# D9X_v41.net
KiCad netlist of a schematic drawn in EAGLE
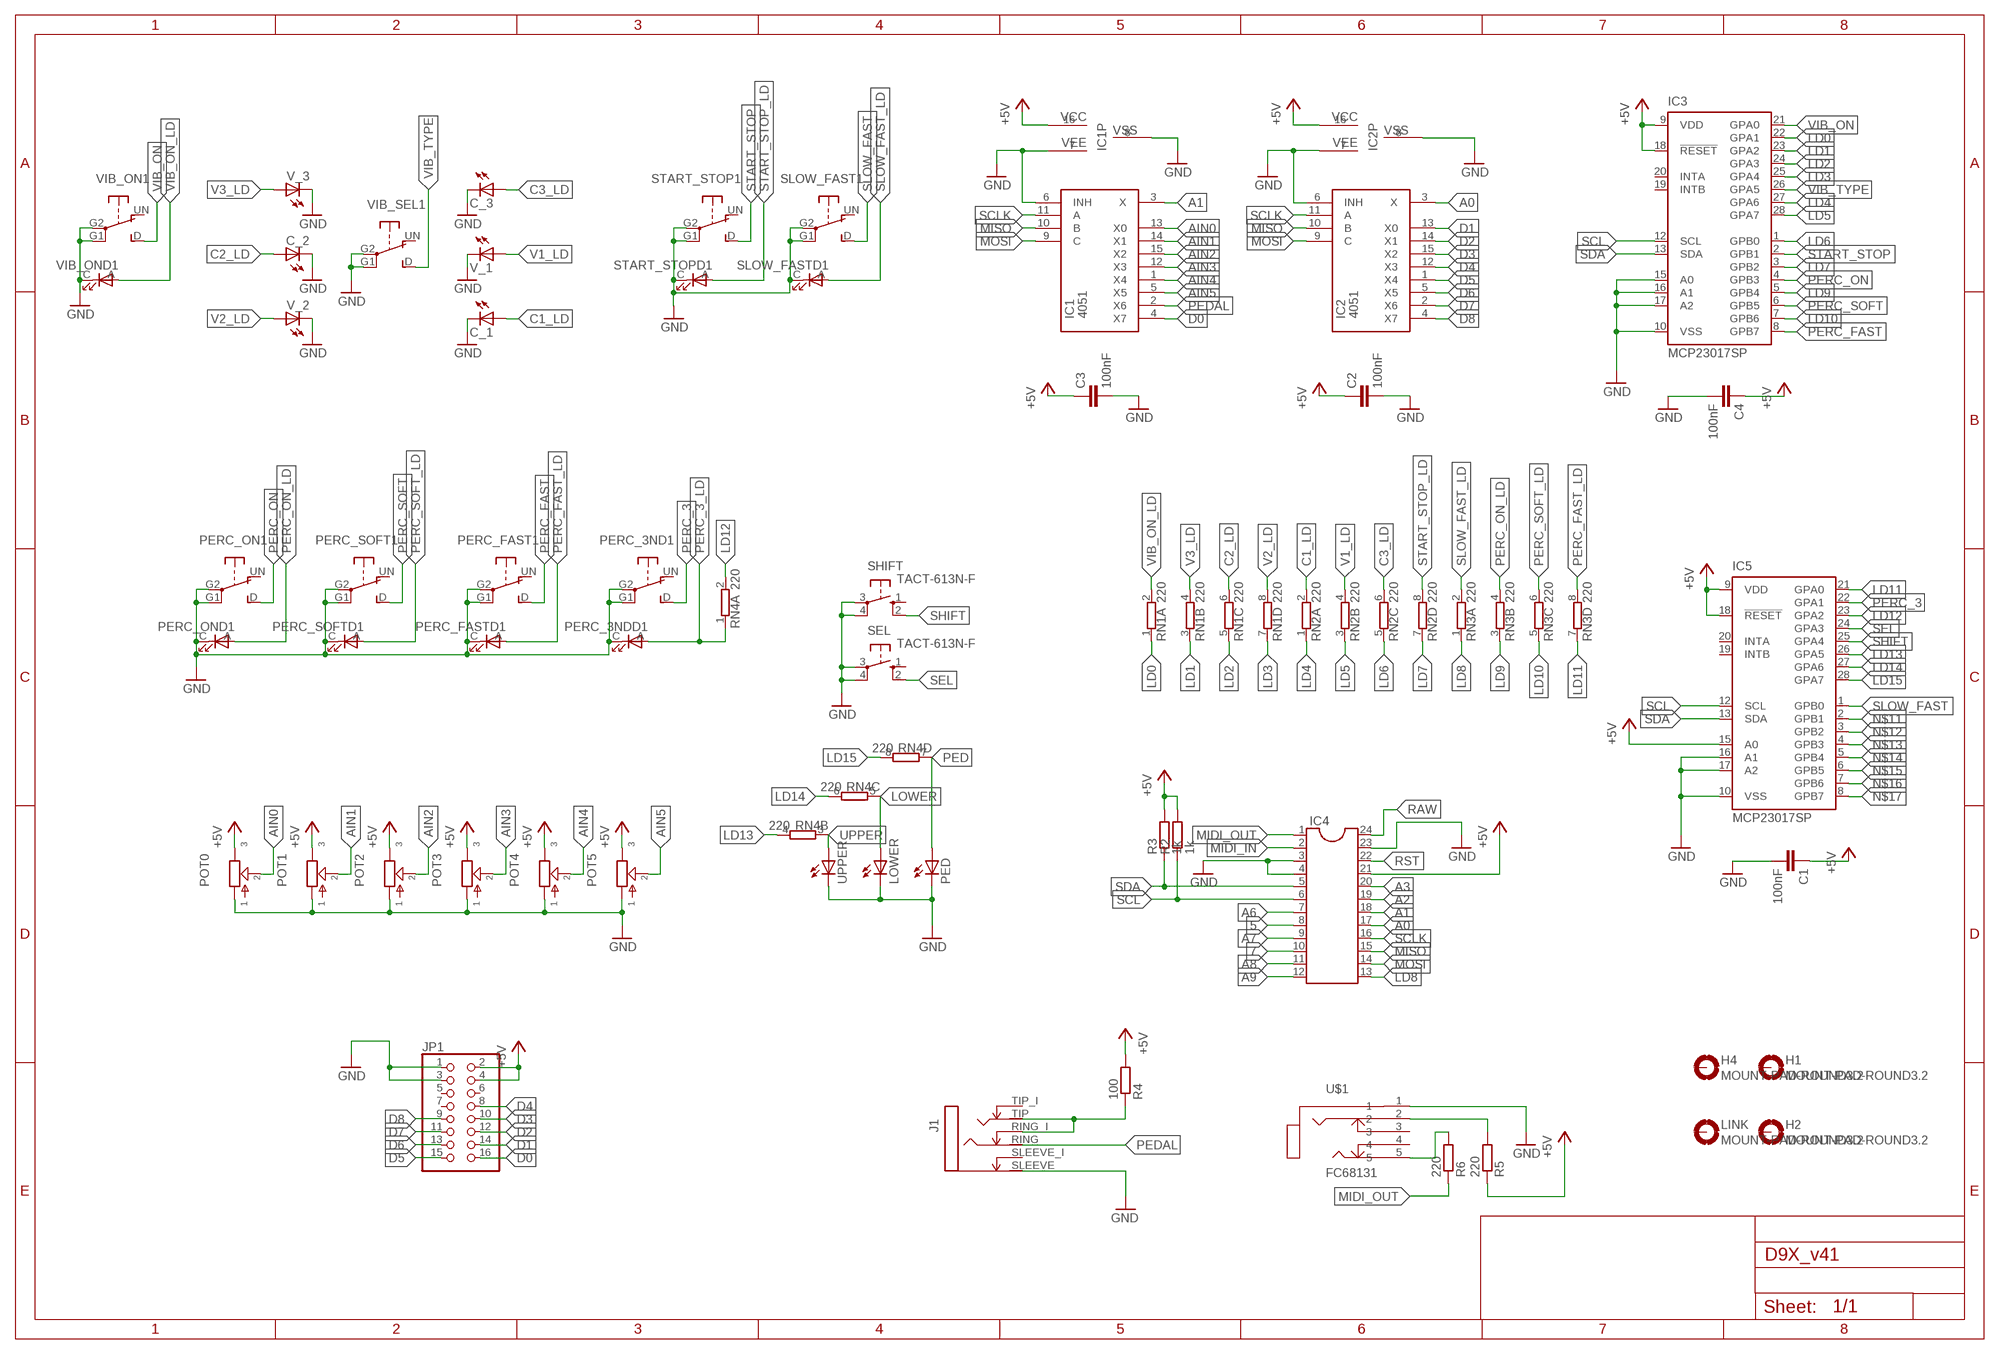
[diagram p0: schematic, sheet 1]

(export (version "E")
  (design (tool "Eeschema 10.0.6"))
  (components
    (comp (ref "C1")
      (value "100nF")
      (footprint "eagle-import:C050-024X044")
      (libsource (lib "eagle-import") (part "C-EU050-024X044"))
    )
    (comp (ref "C2")
      (value "100nF")
      (footprint "eagle-import:C050-024X044")
      (libsource (lib "eagle-import") (part "C-EU050-024X044"))
    )
    (comp (ref "C3")
      (value "100nF")
      (footprint "eagle-import:C050-024X044")
      (libsource (lib "eagle-import") (part "C-EU050-024X044"))
    )
    (comp (ref "C4")
      (value "100nF")
      (footprint "eagle-import:C050-024X044")
      (libsource (lib "eagle-import") (part "C-EU050-024X044"))
    )
    (comp (ref "C_1")
      (value "LED3MM")
      (footprint "eagle-import:LED3MM")
      (libsource (lib "eagle-import") (part "LED3MM"))
    )
    (comp (ref "C_2")
      (value "LED3MM")
      (footprint "eagle-import:LED3MM")
      (libsource (lib "eagle-import") (part "LED3MM"))
    )
    (comp (ref "C_3")
      (value "LED3MM")
      (footprint "eagle-import:LED3MM")
      (libsource (lib "eagle-import") (part "LED3MM"))
    )
    (comp (ref "H1")
      (value "MOUNT-PAD-ROUND3.2")
      (footprint "eagle-import:3,2-PAD")
      (libsource (lib "eagle-import") (part "MOUNT-PAD-ROUND3.2"))
    )
    (comp (ref "H2")
      (value "MOUNT-PAD-ROUND3.2")
      (footprint "eagle-import:3,2-PAD")
      (libsource (lib "eagle-import") (part "MOUNT-PAD-ROUND3.2"))
    )
    (comp (ref "H4")
      (value "MOUNT-PAD-ROUND3.2")
      (footprint "eagle-import:3,2-PAD")
      (libsource (lib "eagle-import") (part "MOUNT-PAD-ROUND3.2"))
    )
    (comp (ref "IC1")
      (value "4051")
      (footprint "eagle-import:DIL16")
      (libsource (lib "eagle-import") (part "4051"))
    )
    (comp (ref "IC2")
      (value "4051")
      (footprint "eagle-import:DIL16")
      (libsource (lib "eagle-import") (part "4051"))
    )
    (comp (ref "IC3")
      (value "MCP23017SP")
      (footprint "eagle-import:DIL28-3")
      (fields (field (name "MF") "MICROCHIP") (field (name "MPN") "MCP23017-E/SP"))
      (libsource (lib "eagle-import") (part "MCP23017SP"))
    )
    (comp (ref "IC4")
      (value "DIL24-6")
      (footprint "eagle-import:DIL24-6")
      (libsource (lib "eagle-import") (part "DIL24-6"))
    )
    (comp (ref "IC5")
      (value "MCP23017SP")
      (footprint "eagle-import:DIL28-3")
      (fields (field (name "MF") "MICROCHIP") (field (name "MPN") "MCP23017-E/SP"))
      (libsource (lib "eagle-import") (part "MCP23017SP"))
    )
    (comp (ref "J1")
      (value "STEREOSWJACK_ST_TRS_INT")
      (footprint "eagle-import:ST_JACK_TRS_INT")
      (libsource (lib "eagle-import") (part "STEREOSWJACK_ST_TRS_INT"))
    )
    (comp (ref "JP1")
      (value "PINHD-2X8")
      (footprint "eagle-import:2X08")
      (libsource (lib "eagle-import") (part "PINHD-2X8"))
    )
    (comp (ref "LINK")
      (value "MOUNT-PAD-ROUND3.2")
      (footprint "eagle-import:3,2-PAD")
      (libsource (lib "eagle-import") (part "MOUNT-PAD-ROUND3.2"))
    )
    (comp (ref "LOWER")
      (value "LED3MM")
      (footprint "eagle-import:LED3MM")
      (libsource (lib "eagle-import") (part "LED3MM"))
    )
    (comp (ref "PED")
      (value "LED3MM")
      (footprint "eagle-import:LED3MM")
      (libsource (lib "eagle-import") (part "LED3MM"))
    )
    (comp (ref "PERC_3ND")
      (value "SRKLSHANPU")
      (footprint "eagle-import:SP86N-A1-5-01")
      (libsource (lib "eagle-import") (part "SRKLSHANPU"))
    )
    (comp (ref "PERC_FAST")
      (value "SRKLSHANPU")
      (footprint "eagle-import:SP86N-A1-5-01")
      (libsource (lib "eagle-import") (part "SRKLSHANPU"))
    )
    (comp (ref "PERC_ON")
      (value "SRKLSHANPU")
      (footprint "eagle-import:SP86N-A1-5-01")
      (libsource (lib "eagle-import") (part "SRKLSHANPU"))
    )
    (comp (ref "PERC_SOFT")
      (value "SRKLSHANPU")
      (footprint "eagle-import:SP86N-A1-5-01")
      (libsource (lib "eagle-import") (part "SRKLSHANPU"))
    )
    (comp (ref "POT0")
      (value "POT-EU12MM")
      (footprint "eagle-import:RV120DF-40B1-(L)K")
      (libsource (lib "eagle-import") (part "POT-EU12MM"))
    )
    (comp (ref "POT1")
      (value "POT-EU12MM")
      (footprint "eagle-import:RV120DF-40B1-(L)K")
      (libsource (lib "eagle-import") (part "POT-EU12MM"))
    )
    (comp (ref "POT2")
      (value "POT-EU12MM")
      (footprint "eagle-import:RV120DF-40B1-(L)K")
      (libsource (lib "eagle-import") (part "POT-EU12MM"))
    )
    (comp (ref "POT3")
      (value "POT-EU12MM")
      (footprint "eagle-import:RV120DF-40B1-(L)K")
      (libsource (lib "eagle-import") (part "POT-EU12MM"))
    )
    (comp (ref "POT4")
      (value "POT-EU12MM")
      (footprint "eagle-import:RV120DF-40B1-(L)K")
      (libsource (lib "eagle-import") (part "POT-EU12MM"))
    )
    (comp (ref "POT5")
      (value "POT-EU12MM")
      (footprint "eagle-import:RV120DF-40B1-(L)K")
      (libsource (lib "eagle-import") (part "POT-EU12MM"))
    )
    (comp (ref "R2")
      (value "1k")
      (footprint "eagle-import:0204_7")
      (libsource (lib "eagle-import") (part "R-EU_0204/7"))
    )
    (comp (ref "R3")
      (value "1k")
      (footprint "eagle-import:0204_7")
      (libsource (lib "eagle-import") (part "R-EU_0204/7"))
    )
    (comp (ref "R4")
      (value "100")
      (footprint "eagle-import:0204_7")
      (libsource (lib "eagle-import") (part "R-EU_0204/7"))
    )
    (comp (ref "R5")
      (value "220")
      (footprint "eagle-import:0204_7")
      (libsource (lib "eagle-import") (part "R-EU_0204/7"))
    )
    (comp (ref "R6")
      (value "220")
      (footprint "eagle-import:0204_7")
      (libsource (lib "eagle-import") (part "R-EU_0204/7"))
    )
    (comp (ref "RN1")
      (value "220")
      (footprint "eagle-import:SIL8")
      (libsource (lib "eagle-import") (part "E4R"))
    )
    (comp (ref "RN2")
      (value "220")
      (footprint "eagle-import:SIL8")
      (libsource (lib "eagle-import") (part "E4R"))
    )
    (comp (ref "RN3")
      (value "220")
      (footprint "eagle-import:SIL8")
      (libsource (lib "eagle-import") (part "E4R"))
    )
    (comp (ref "RN4")
      (value "220")
      (footprint "eagle-import:SIL8")
      (libsource (lib "eagle-import") (part "E4R"))
    )
    (comp (ref "SEL")
      (value "TACT-613N-F")
      (footprint "eagle-import:B3F-10XX")
      (fields (field (name "MPN") "B3F-1000"))
      (libsource (lib "eagle-import") (part "10-XX"))
    )
    (comp (ref "SHIFT")
      (value "TACT-613N-F")
      (footprint "eagle-import:B3F-10XX")
      (fields (field (name "MPN") "B3F-1000"))
      (libsource (lib "eagle-import") (part "10-XX"))
    )
    (comp (ref "SLOW_FAST")
      (value "SRKLSHANPU")
      (footprint "eagle-import:SP86N-A1-5-01")
      (libsource (lib "eagle-import") (part "SRKLSHANPU"))
    )
    (comp (ref "START_STOP")
      (value "SRKLSHANPU")
      (footprint "eagle-import:SP86N-A1-5-01")
      (libsource (lib "eagle-import") (part "SRKLSHANPU"))
    )
    (comp (ref "U$1")
      (value "FC68131")
      (footprint "eagle-import:FC68131-5P")
      (libsource (lib "eagle-import") (part "FC68131"))
    )
    (comp (ref "UPPER")
      (value "LED3MM")
      (footprint "eagle-import:LED3MM")
      (libsource (lib "eagle-import") (part "LED3MM"))
    )
    (comp (ref "VIB_ON")
      (value "SRKLSHANPU")
      (footprint "eagle-import:SP86N-A1-5-01")
      (libsource (lib "eagle-import") (part "SRKLSHANPU"))
    )
    (comp (ref "VIB_SEL")
      (value "SRKLSHANPU")
      (footprint "eagle-import:SP86N-A1-5-01")
      (libsource (lib "eagle-import") (part "SRKLSHANPU"))
    )
    (comp (ref "V_1")
      (value "LED3MM")
      (footprint "eagle-import:LED3MM")
      (libsource (lib "eagle-import") (part "LED3MM"))
    )
    (comp (ref "V_2")
      (value "LED3MM")
      (footprint "eagle-import:LED3MM")
      (libsource (lib "eagle-import") (part "LED3MM"))
    )
    (comp (ref "V_3")
      (value "LED3MM")
      (footprint "eagle-import:LED3MM")
      (libsource (lib "eagle-import") (part "LED3MM"))
    )
  )
  (nets
    (net (code "1") (name "+5V") (class "Default")
      (node (ref "C1") (pin "1") (pinfunction "1_1") (pintype "passive"))
      (node (ref "C2") (pin "1") (pinfunction "1_1") (pintype "passive"))
      (node (ref "C3") (pin "1") (pinfunction "1_1") (pintype "passive"))
      (node (ref "C4") (pin "1") (pinfunction "1_1") (pintype "passive"))
      (node (ref "IC1") (pin "16") (pinfunction "VCC_16") (pintype "power_in"))
      (node (ref "IC2") (pin "16") (pinfunction "VCC_16") (pintype "power_in"))
      (node (ref "IC3") (pin "18") (pinfunction "~{RESET}_18") (pintype "input"))
      (node (ref "IC3") (pin "9") (pinfunction "VDD_9") (pintype "power_in"))
      (node (ref "IC4") (pin "21") (pinfunction "21_21") (pintype "passive"))
      (node (ref "IC5") (pin "15") (pinfunction "A0_15") (pintype "input"))
      (node (ref "IC5") (pin "18") (pinfunction "~{RESET}_18") (pintype "input"))
      (node (ref "IC5") (pin "9") (pinfunction "VDD_9") (pintype "power_in"))
      (node (ref "JP1") (pin "2") (pinfunction "2_2") (pintype "passive"))
      (node (ref "JP1") (pin "4") (pinfunction "4_4") (pintype "passive"))
      (node (ref "POT0") (pin "3") (pinfunction "3_3") (pintype "passive"))
      (node (ref "POT1") (pin "3") (pinfunction "3_3") (pintype "passive"))
      (node (ref "POT2") (pin "3") (pinfunction "3_3") (pintype "passive"))
      (node (ref "POT3") (pin "3") (pinfunction "3_3") (pintype "passive"))
      (node (ref "POT4") (pin "3") (pinfunction "3_3") (pintype "passive"))
      (node (ref "POT5") (pin "3") (pinfunction "3_3") (pintype "passive"))
      (node (ref "R2") (pin "2") (pinfunction "2_2") (pintype "passive"))
      (node (ref "R3") (pin "2") (pinfunction "2_2") (pintype "passive"))
      (node (ref "R4") (pin "2") (pinfunction "2_2") (pintype "passive"))
      (node (ref "R5") (pin "1") (pinfunction "1_1") (pintype "passive"))
    )
    (net (code "2") (name "5") (class "Default")
      (node (ref "IC4") (pin "8") (pinfunction "8_8") (pintype "passive"))
    )
    (net (code "3") (name "7") (class "Default")
      (node (ref "IC4") (pin "10") (pinfunction "10_10") (pintype "passive"))
    )
    (net (code "4") (name "A0") (class "Default")
      (node (ref "IC2") (pin "3") (pinfunction "X_3") (pintype "bidirectional"))
      (node (ref "IC4") (pin "17") (pinfunction "17_17") (pintype "passive"))
    )
    (net (code "5") (name "A1") (class "Default")
      (node (ref "IC1") (pin "3") (pinfunction "X_3") (pintype "bidirectional"))
      (node (ref "IC4") (pin "18") (pinfunction "18_18") (pintype "passive"))
    )
    (net (code "6") (name "A2") (class "Default")
      (node (ref "IC4") (pin "19") (pinfunction "19_19") (pintype "passive"))
    )
    (net (code "7") (name "A3") (class "Default")
      (node (ref "IC4") (pin "20") (pinfunction "20_20") (pintype "passive"))
    )
    (net (code "8") (name "A6") (class "Default")
      (node (ref "IC4") (pin "7") (pinfunction "7_7") (pintype "passive"))
    )
    (net (code "9") (name "A7") (class "Default")
      (node (ref "IC4") (pin "9") (pinfunction "9_9") (pintype "passive"))
    )
    (net (code "10") (name "A8") (class "Default")
      (node (ref "IC4") (pin "11") (pinfunction "11_11") (pintype "passive"))
    )
    (net (code "11") (name "A9") (class "Default")
      (node (ref "IC4") (pin "12") (pinfunction "12_12") (pintype "passive"))
    )
    (net (code "12") (name "AIN0") (class "Default")
      (node (ref "IC1") (pin "13") (pinfunction "X0_13") (pintype "bidirectional"))
      (node (ref "POT0") (pin "2") (pinfunction "2_2") (pintype "passive"))
    )
    (net (code "13") (name "AIN1") (class "Default")
      (node (ref "IC1") (pin "14") (pinfunction "X1_14") (pintype "bidirectional"))
      (node (ref "POT1") (pin "2") (pinfunction "2_2") (pintype "passive"))
    )
    (net (code "14") (name "AIN2") (class "Default")
      (node (ref "IC1") (pin "15") (pinfunction "X2_15") (pintype "bidirectional"))
      (node (ref "POT2") (pin "2") (pinfunction "2_2") (pintype "passive"))
    )
    (net (code "15") (name "AIN3") (class "Default")
      (node (ref "IC1") (pin "12") (pinfunction "X3_12") (pintype "bidirectional"))
      (node (ref "POT3") (pin "2") (pinfunction "2_2") (pintype "passive"))
    )
    (net (code "16") (name "AIN4") (class "Default")
      (node (ref "IC1") (pin "1") (pinfunction "X4_1") (pintype "bidirectional"))
      (node (ref "POT4") (pin "2") (pinfunction "2_2") (pintype "passive"))
    )
    (net (code "17") (name "AIN5") (class "Default")
      (node (ref "IC1") (pin "5") (pinfunction "X5_5") (pintype "bidirectional"))
      (node (ref "POT5") (pin "2") (pinfunction "2_2") (pintype "passive"))
    )
    (net (code "18") (name "C1_LD") (class "Default")
      (node (ref "C_1") (pin "A") (pinfunction "A_A") (pintype "passive"))
      (node (ref "RN2") (pin "2") (pinfunction "2_2") (pintype "passive"))
    )
    (net (code "19") (name "C2_LD") (class "Default")
      (node (ref "C_2") (pin "A") (pinfunction "A_A") (pintype "passive"))
      (node (ref "RN1") (pin "6") (pinfunction "2_6") (pintype "passive"))
    )
    (net (code "20") (name "C3_LD") (class "Default")
      (node (ref "C_3") (pin "A") (pinfunction "A_A") (pintype "passive"))
      (node (ref "RN2") (pin "6") (pinfunction "2_6") (pintype "passive"))
    )
    (net (code "21") (name "D0") (class "Default")
      (node (ref "IC1") (pin "4") (pinfunction "X7_4") (pintype "bidirectional"))
      (node (ref "JP1") (pin "16") (pinfunction "16_16") (pintype "passive"))
    )
    (net (code "22") (name "D1") (class "Default")
      (node (ref "IC2") (pin "13") (pinfunction "X0_13") (pintype "bidirectional"))
      (node (ref "JP1") (pin "14") (pinfunction "14_14") (pintype "passive"))
    )
    (net (code "23") (name "D2") (class "Default")
      (node (ref "IC2") (pin "14") (pinfunction "X1_14") (pintype "bidirectional"))
      (node (ref "JP1") (pin "12") (pinfunction "12_12") (pintype "passive"))
    )
    (net (code "24") (name "D3") (class "Default")
      (node (ref "IC2") (pin "15") (pinfunction "X2_15") (pintype "bidirectional"))
      (node (ref "JP1") (pin "10") (pinfunction "10_10") (pintype "passive"))
    )
    (net (code "25") (name "D4") (class "Default")
      (node (ref "IC2") (pin "12") (pinfunction "X3_12") (pintype "bidirectional"))
      (node (ref "JP1") (pin "8") (pinfunction "8_8") (pintype "passive"))
    )
    (net (code "26") (name "D5") (class "Default")
      (node (ref "IC2") (pin "1") (pinfunction "X4_1") (pintype "bidirectional"))
      (node (ref "JP1") (pin "15") (pinfunction "15_15") (pintype "passive"))
    )
    (net (code "27") (name "D6") (class "Default")
      (node (ref "IC2") (pin "5") (pinfunction "X5_5") (pintype "bidirectional"))
      (node (ref "JP1") (pin "13") (pinfunction "13_13") (pintype "passive"))
    )
    (net (code "28") (name "D7") (class "Default")
      (node (ref "IC2") (pin "2") (pinfunction "X6_2") (pintype "bidirectional"))
      (node (ref "JP1") (pin "11") (pinfunction "11_11") (pintype "passive"))
    )
    (net (code "29") (name "D8") (class "Default")
      (node (ref "IC2") (pin "4") (pinfunction "X7_4") (pintype "bidirectional"))
      (node (ref "JP1") (pin "9") (pinfunction "9_9") (pintype "passive"))
    )
    (net (code "30") (name "GND") (class "Default")
      (node (ref "C1") (pin "2") (pinfunction "2_2") (pintype "passive"))
      (node (ref "C2") (pin "2") (pinfunction "2_2") (pintype "passive"))
      (node (ref "C3") (pin "2") (pinfunction "2_2") (pintype "passive"))
      (node (ref "C4") (pin "2") (pinfunction "2_2") (pintype "passive"))
      (node (ref "C_1") (pin "K") (pinfunction "C_K") (pintype "passive"))
      (node (ref "C_2") (pin "K") (pinfunction "C_K") (pintype "passive"))
      (node (ref "C_3") (pin "K") (pinfunction "C_K") (pintype "passive"))
      (node (ref "IC1") (pin "6") (pinfunction "INH_6") (pintype "input"))
      (node (ref "IC1") (pin "7") (pinfunction "VEE_7") (pintype "power_in"))
      (node (ref "IC1") (pin "8") (pinfunction "VSS_8") (pintype "power_in"))
      (node (ref "IC2") (pin "6") (pinfunction "INH_6") (pintype "input"))
      (node (ref "IC2") (pin "7") (pinfunction "VEE_7") (pintype "power_in"))
      (node (ref "IC2") (pin "8") (pinfunction "VSS_8") (pintype "power_in"))
      (node (ref "IC3") (pin "10") (pinfunction "VSS_10") (pintype "power_in"))
      (node (ref "IC3") (pin "15") (pinfunction "A0_15") (pintype "input"))
      (node (ref "IC3") (pin "16") (pinfunction "A1_16") (pintype "input"))
      (node (ref "IC3") (pin "17") (pinfunction "A2_17") (pintype "input"))
      (node (ref "IC4") (pin "23") (pinfunction "23_23") (pintype "passive"))
      (node (ref "IC4") (pin "3") (pinfunction "3_3") (pintype "passive"))
      (node (ref "IC4") (pin "4") (pinfunction "4_4") (pintype "passive"))
      (node (ref "IC5") (pin "10") (pinfunction "VSS_10") (pintype "power_in"))
      (node (ref "IC5") (pin "16") (pinfunction "A1_16") (pintype "input"))
      (node (ref "IC5") (pin "17") (pinfunction "A2_17") (pintype "input"))
      (node (ref "J1") (pin "SLEEVE") (pinfunction "S_SLEEVE") (pintype "passive"))
      (node (ref "JP1") (pin "1") (pinfunction "1_1") (pintype "passive"))
      (node (ref "JP1") (pin "3") (pinfunction "3_3") (pintype "passive"))
      (node (ref "LOWER") (pin "K") (pinfunction "C_K") (pintype "passive"))
      (node (ref "PED") (pin "K") (pinfunction "C_K") (pintype "passive"))
      (node (ref "PERC_3ND") (pin "C") (pinfunction "C_C") (pintype "passive"))
      (node (ref "PERC_3ND") (pin "G1") (pinfunction "P_G1") (pintype "passive"))
      (node (ref "PERC_3ND") (pin "G2") (pinfunction "P_G2") (pintype "passive"))
      (node (ref "PERC_FAST") (pin "C") (pinfunction "C_C") (pintype "passive"))
      (node (ref "PERC_FAST") (pin "G1") (pinfunction "P_G1") (pintype "passive"))
      (node (ref "PERC_FAST") (pin "G2") (pinfunction "P_G2") (pintype "passive"))
      (node (ref "PERC_ON") (pin "C") (pinfunction "C_C") (pintype "passive"))
      (node (ref "PERC_ON") (pin "G1") (pinfunction "P_G1") (pintype "passive"))
      (node (ref "PERC_ON") (pin "G2") (pinfunction "P_G2") (pintype "passive"))
      (node (ref "PERC_SOFT") (pin "C") (pinfunction "C_C") (pintype "passive"))
      (node (ref "PERC_SOFT") (pin "G1") (pinfunction "P_G1") (pintype "passive"))
      (node (ref "PERC_SOFT") (pin "G2") (pinfunction "P_G2") (pintype "passive"))
      (node (ref "POT0") (pin "1") (pinfunction "1_1") (pintype "passive"))
      (node (ref "POT1") (pin "1") (pinfunction "1_1") (pintype "passive"))
      (node (ref "POT2") (pin "1") (pinfunction "1_1") (pintype "passive"))
      (node (ref "POT3") (pin "1") (pinfunction "1_1") (pintype "passive"))
      (node (ref "POT4") (pin "1") (pinfunction "1_1") (pintype "passive"))
      (node (ref "POT5") (pin "1") (pinfunction "1_1") (pintype "passive"))
      (node (ref "SEL") (pin "3") (pinfunction "P_3") (pintype "passive"))
      (node (ref "SEL") (pin "4") (pinfunction "P1_4") (pintype "passive"))
      (node (ref "SHIFT") (pin "3") (pinfunction "P_3") (pintype "passive"))
      (node (ref "SHIFT") (pin "4") (pinfunction "P1_4") (pintype "passive"))
      (node (ref "SLOW_FAST") (pin "C") (pinfunction "C_C") (pintype "passive"))
      (node (ref "SLOW_FAST") (pin "G1") (pinfunction "P_G1") (pintype "passive"))
      (node (ref "SLOW_FAST") (pin "G2") (pinfunction "P_G2") (pintype "passive"))
      (node (ref "START_STOP") (pin "C") (pinfunction "C_C") (pintype "passive"))
      (node (ref "START_STOP") (pin "G1") (pinfunction "P_G1") (pintype "passive"))
      (node (ref "START_STOP") (pin "G2") (pinfunction "P_G2") (pintype "passive"))
      (node (ref "U$1") (pin "1") (pinfunction "1_1") (pintype "bidirectional"))
      (node (ref "UPPER") (pin "K") (pinfunction "C_K") (pintype "passive"))
      (node (ref "VIB_ON") (pin "C") (pinfunction "C_C") (pintype "passive"))
      (node (ref "VIB_ON") (pin "G1") (pinfunction "P_G1") (pintype "passive"))
      (node (ref "VIB_ON") (pin "G2") (pinfunction "P_G2") (pintype "passive"))
      (node (ref "VIB_SEL") (pin "G1") (pinfunction "P_G1") (pintype "passive"))
      (node (ref "VIB_SEL") (pin "G2") (pinfunction "P_G2") (pintype "passive"))
      (node (ref "V_1") (pin "K") (pinfunction "C_K") (pintype "passive"))
      (node (ref "V_2") (pin "K") (pinfunction "C_K") (pintype "passive"))
      (node (ref "V_3") (pin "K") (pinfunction "C_K") (pintype "passive"))
    )
    (net (code "31") (name "LD0") (class "Default")
      (node (ref "IC3") (pin "22") (pinfunction "GPA1_22") (pintype "bidirectional"))
      (node (ref "RN1") (pin "1") (pinfunction "1_1") (pintype "passive"))
    )
    (net (code "32") (name "LD1") (class "Default")
      (node (ref "IC3") (pin "23") (pinfunction "GPA2_23") (pintype "bidirectional"))
      (node (ref "RN1") (pin "3") (pinfunction "1_3") (pintype "passive"))
    )
    (net (code "33") (name "LD2") (class "Default")
      (node (ref "IC3") (pin "24") (pinfunction "GPA3_24") (pintype "bidirectional"))
      (node (ref "RN1") (pin "5") (pinfunction "1_5") (pintype "passive"))
    )
    (net (code "34") (name "LD3") (class "Default")
      (node (ref "IC3") (pin "25") (pinfunction "GPA4_25") (pintype "bidirectional"))
      (node (ref "RN1") (pin "7") (pinfunction "1_7") (pintype "passive"))
    )
    (net (code "35") (name "LD4") (class "Default")
      (node (ref "IC3") (pin "27") (pinfunction "GPA6_27") (pintype "bidirectional"))
      (node (ref "RN2") (pin "1") (pinfunction "1_1") (pintype "passive"))
    )
    (net (code "36") (name "LD5") (class "Default")
      (node (ref "IC3") (pin "28") (pinfunction "GPA7_28") (pintype "bidirectional"))
      (node (ref "RN2") (pin "3") (pinfunction "1_3") (pintype "passive"))
    )
    (net (code "37") (name "LD6") (class "Default")
      (node (ref "IC3") (pin "1") (pinfunction "GPB0_1") (pintype "bidirectional"))
      (node (ref "RN2") (pin "5") (pinfunction "1_5") (pintype "passive"))
    )
    (net (code "38") (name "LD7") (class "Default")
      (node (ref "IC3") (pin "3") (pinfunction "GPB2_3") (pintype "bidirectional"))
      (node (ref "RN2") (pin "7") (pinfunction "1_7") (pintype "passive"))
    )
    (net (code "39") (name "LD8") (class "Default")
      (node (ref "IC4") (pin "13") (pinfunction "13_13") (pintype "passive"))
      (node (ref "RN3") (pin "1") (pinfunction "1_1") (pintype "passive"))
    )
    (net (code "40") (name "LD9") (class "Default")
      (node (ref "IC3") (pin "5") (pinfunction "GPB4_5") (pintype "bidirectional"))
      (node (ref "RN3") (pin "3") (pinfunction "1_3") (pintype "passive"))
    )
    (net (code "41") (name "LD10") (class "Default")
      (node (ref "IC3") (pin "7") (pinfunction "GPB6_7") (pintype "bidirectional"))
      (node (ref "RN3") (pin "5") (pinfunction "1_5") (pintype "passive"))
    )
    (net (code "42") (name "LD11") (class "Default")
      (node (ref "IC5") (pin "21") (pinfunction "GPA0_21") (pintype "bidirectional"))
      (node (ref "RN3") (pin "7") (pinfunction "1_7") (pintype "passive"))
    )
    (net (code "43") (name "LD12") (class "Default")
      (node (ref "IC5") (pin "23") (pinfunction "GPA2_23") (pintype "bidirectional"))
      (node (ref "RN4") (pin "2") (pinfunction "2_2") (pintype "passive"))
    )
    (net (code "44") (name "LD13") (class "Default")
      (node (ref "IC5") (pin "26") (pinfunction "GPA5_26") (pintype "bidirectional"))
      (node (ref "RN4") (pin "4") (pinfunction "2_4") (pintype "passive"))
    )
    (net (code "45") (name "LD14") (class "Default")
      (node (ref "IC5") (pin "27") (pinfunction "GPA6_27") (pintype "bidirectional"))
      (node (ref "RN4") (pin "6") (pinfunction "2_6") (pintype "passive"))
    )
    (net (code "46") (name "LD15") (class "Default")
      (node (ref "IC5") (pin "28") (pinfunction "GPA7_28") (pintype "bidirectional"))
      (node (ref "RN4") (pin "8") (pinfunction "2_8") (pintype "passive"))
    )
    (net (code "47") (name "LOWER") (class "Default")
      (node (ref "LOWER") (pin "A") (pinfunction "A_A") (pintype "passive"))
      (node (ref "RN4") (pin "5") (pinfunction "1_5") (pintype "passive"))
    )
    (net (code "48") (name "MIDI_IN") (class "Default")
      (node (ref "IC4") (pin "2") (pinfunction "2_2") (pintype "passive"))
    )
    (net (code "49") (name "MIDI_OUT") (class "Default")
      (node (ref "IC4") (pin "1") (pinfunction "1_1") (pintype "passive"))
      (node (ref "R6") (pin "1") (pinfunction "1_1") (pintype "passive"))
    )
    (net (code "50") (name "MISO") (class "Default")
      (node (ref "IC1") (pin "10") (pinfunction "B_10") (pintype "input"))
      (node (ref "IC2") (pin "10") (pinfunction "B_10") (pintype "input"))
      (node (ref "IC4") (pin "15") (pinfunction "15_15") (pintype "passive"))
    )
    (net (code "51") (name "MOSI") (class "Default")
      (node (ref "IC1") (pin "9") (pinfunction "C_9") (pintype "input"))
      (node (ref "IC2") (pin "9") (pinfunction "C_9") (pintype "input"))
      (node (ref "IC4") (pin "14") (pinfunction "14_14") (pintype "passive"))
    )
    (net (code "52") (name "N$11") (class "Default")
      (node (ref "IC5") (pin "2") (pinfunction "GPB1_2") (pintype "bidirectional"))
    )
    (net (code "53") (name "N$12") (class "Default")
      (node (ref "IC5") (pin "3") (pinfunction "GPB2_3") (pintype "bidirectional"))
    )
    (net (code "54") (name "N$13") (class "Default")
      (node (ref "IC5") (pin "4") (pinfunction "GPB3_4") (pintype "bidirectional"))
    )
    (net (code "55") (name "N$14") (class "Default")
      (node (ref "IC5") (pin "5") (pinfunction "GPB4_5") (pintype "bidirectional"))
    )
    (net (code "56") (name "N$15") (class "Default")
      (node (ref "IC5") (pin "6") (pinfunction "GPB5_6") (pintype "bidirectional"))
    )
    (net (code "57") (name "N$16") (class "Default")
      (node (ref "IC5") (pin "7") (pinfunction "GPB6_7") (pintype "bidirectional"))
    )
    (net (code "58") (name "N$17") (class "Default")
      (node (ref "IC5") (pin "8") (pinfunction "GPB7_8") (pintype "bidirectional"))
    )
    (net (code "59") (name "Net-(J1-RN)") (class "Default")
      (node (ref "J1") (pin "RING_I") (pinfunction "RN_RING_I") (pintype "passive"))
      (node (ref "J1") (pin "TIP") (pinfunction "T_TIP") (pintype "passive"))
      (node (ref "R4") (pin "1") (pinfunction "1_1") (pintype "passive"))
    )
    (net (code "60") (name "Net-(R5-Pad2)") (class "Default")
      (node (ref "R5") (pin "2") (pinfunction "2_2") (pintype "passive"))
      (node (ref "U$1") (pin "2") (pinfunction "2_2") (pintype "bidirectional"))
    )
    (net (code "61") (name "Net-(R6-Pad2)") (class "Default")
      (node (ref "R6") (pin "2") (pinfunction "2_2") (pintype "passive"))
      (node (ref "U$1") (pin "5") (pinfunction "5_5") (pintype "bidirectional"))
    )
    (net (code "62") (name "PED") (class "Default")
      (node (ref "PED") (pin "A") (pinfunction "A_A") (pintype "passive"))
      (node (ref "RN4") (pin "7") (pinfunction "1_7") (pintype "passive"))
    )
    (net (code "63") (name "PEDAL") (class "Default")
      (node (ref "IC1") (pin "2") (pinfunction "X6_2") (pintype "bidirectional"))
      (node (ref "J1") (pin "RING") (pinfunction "R_RING") (pintype "passive"))
    )
    (net (code "64") (name "PERC_3") (class "Default")
      (node (ref "IC5") (pin "22") (pinfunction "GPA1_22") (pintype "bidirectional"))
      (node (ref "PERC_3ND") (pin "D") (pinfunction "S_D") (pintype "passive"))
    )
    (net (code "65") (name "PERC_3_LD") (class "Default")
      (node (ref "PERC_3ND") (pin "A") (pinfunction "A_A") (pintype "passive"))
      (node (ref "RN4") (pin "1") (pinfunction "1_1") (pintype "passive"))
    )
    (net (code "66") (name "PERC_FAST") (class "Default")
      (node (ref "IC3") (pin "8") (pinfunction "GPB7_8") (pintype "bidirectional"))
      (node (ref "PERC_FAST") (pin "D") (pinfunction "S_D") (pintype "passive"))
    )
    (net (code "67") (name "PERC_FAST_LD") (class "Default")
      (node (ref "PERC_FAST") (pin "A") (pinfunction "A_A") (pintype "passive"))
      (node (ref "RN3") (pin "8") (pinfunction "2_8") (pintype "passive"))
    )
    (net (code "68") (name "PERC_ON") (class "Default")
      (node (ref "IC3") (pin "4") (pinfunction "GPB3_4") (pintype "bidirectional"))
      (node (ref "PERC_ON") (pin "D") (pinfunction "S_D") (pintype "passive"))
    )
    (net (code "69") (name "PERC_ON_LD") (class "Default")
      (node (ref "PERC_ON") (pin "A") (pinfunction "A_A") (pintype "passive"))
      (node (ref "RN3") (pin "4") (pinfunction "2_4") (pintype "passive"))
    )
    (net (code "70") (name "PERC_SOFT") (class "Default")
      (node (ref "IC3") (pin "6") (pinfunction "GPB5_6") (pintype "bidirectional"))
      (node (ref "PERC_SOFT") (pin "D") (pinfunction "S_D") (pintype "passive"))
    )
    (net (code "71") (name "PERC_SOFT_LD") (class "Default")
      (node (ref "PERC_SOFT") (pin "A") (pinfunction "A_A") (pintype "passive"))
      (node (ref "RN3") (pin "6") (pinfunction "2_6") (pintype "passive"))
    )
    (net (code "72") (name "RAW") (class "Default")
      (node (ref "IC4") (pin "24") (pinfunction "24_24") (pintype "passive"))
    )
    (net (code "73") (name "RST") (class "Default")
      (node (ref "IC4") (pin "22") (pinfunction "22_22") (pintype "passive"))
    )
    (net (code "74") (name "SCL") (class "Default")
      (node (ref "IC3") (pin "12") (pinfunction "SCL_12") (pintype "input"))
      (node (ref "IC4") (pin "6") (pinfunction "6_6") (pintype "passive"))
      (node (ref "IC5") (pin "12") (pinfunction "SCL_12") (pintype "input"))
      (node (ref "R2") (pin "1") (pinfunction "1_1") (pintype "passive"))
    )
    (net (code "75") (name "SCLK") (class "Default")
      (node (ref "IC1") (pin "11") (pinfunction "A_11") (pintype "input"))
      (node (ref "IC2") (pin "11") (pinfunction "A_11") (pintype "input"))
      (node (ref "IC4") (pin "16") (pinfunction "16_16") (pintype "passive"))
    )
    (net (code "76") (name "SDA") (class "Default")
      (node (ref "IC3") (pin "13") (pinfunction "SDA_13") (pintype "bidirectional"))
      (node (ref "IC4") (pin "5") (pinfunction "5_5") (pintype "passive"))
      (node (ref "IC5") (pin "13") (pinfunction "SDA_13") (pintype "bidirectional"))
      (node (ref "R3") (pin "1") (pinfunction "1_1") (pintype "passive"))
    )
    (net (code "77") (name "SEL") (class "Default")
      (node (ref "IC5") (pin "24") (pinfunction "GPA3_24") (pintype "bidirectional"))
      (node (ref "SEL") (pin "2") (pinfunction "S1_2") (pintype "passive"))
    )
    (net (code "78") (name "SHIFT") (class "Default")
      (node (ref "IC5") (pin "25") (pinfunction "GPA4_25") (pintype "bidirectional"))
      (node (ref "SHIFT") (pin "2") (pinfunction "S1_2") (pintype "passive"))
    )
    (net (code "79") (name "SLOW_FAST") (class "Default")
      (node (ref "IC5") (pin "1") (pinfunction "GPB0_1") (pintype "bidirectional"))
      (node (ref "SLOW_FAST") (pin "D") (pinfunction "S_D") (pintype "passive"))
    )
    (net (code "80") (name "SLOW_FAST_LD") (class "Default")
      (node (ref "RN3") (pin "2") (pinfunction "2_2") (pintype "passive"))
      (node (ref "SLOW_FAST") (pin "A") (pinfunction "A_A") (pintype "passive"))
    )
    (net (code "81") (name "START_STOP") (class "Default")
      (node (ref "IC3") (pin "2") (pinfunction "GPB1_2") (pintype "bidirectional"))
      (node (ref "START_STOP") (pin "D") (pinfunction "S_D") (pintype "passive"))
    )
    (net (code "82") (name "START_STOP_LD") (class "Default")
      (node (ref "RN2") (pin "8") (pinfunction "2_8") (pintype "passive"))
      (node (ref "START_STOP") (pin "A") (pinfunction "A_A") (pintype "passive"))
    )
    (net (code "83") (name "UPPER") (class "Default")
      (node (ref "RN4") (pin "3") (pinfunction "1_3") (pintype "passive"))
      (node (ref "UPPER") (pin "A") (pinfunction "A_A") (pintype "passive"))
    )
    (net (code "84") (name "V1_LD") (class "Default")
      (node (ref "RN2") (pin "4") (pinfunction "2_4") (pintype "passive"))
      (node (ref "V_1") (pin "A") (pinfunction "A_A") (pintype "passive"))
    )
    (net (code "85") (name "V2_LD") (class "Default")
      (node (ref "RN1") (pin "8") (pinfunction "2_8") (pintype "passive"))
      (node (ref "V_2") (pin "A") (pinfunction "A_A") (pintype "passive"))
    )
    (net (code "86") (name "V3_LD") (class "Default")
      (node (ref "RN1") (pin "4") (pinfunction "2_4") (pintype "passive"))
      (node (ref "V_3") (pin "A") (pinfunction "A_A") (pintype "passive"))
    )
    (net (code "87") (name "VIB_ON") (class "Default")
      (node (ref "IC3") (pin "21") (pinfunction "GPA0_21") (pintype "bidirectional"))
      (node (ref "VIB_ON") (pin "D") (pinfunction "S_D") (pintype "passive"))
    )
    (net (code "88") (name "VIB_ON_LD") (class "Default")
      (node (ref "RN1") (pin "2") (pinfunction "2_2") (pintype "passive"))
      (node (ref "VIB_ON") (pin "A") (pinfunction "A_A") (pintype "passive"))
    )
    (net (code "89") (name "VIB_TYPE") (class "Default")
      (node (ref "IC3") (pin "26") (pinfunction "GPA5_26") (pintype "bidirectional"))
      (node (ref "VIB_SEL") (pin "D") (pinfunction "S_D") (pintype "passive"))
    )
    (net (code "90") (name "unconnected-(H1-MOUNT-PadB3,2)") (class "Default")
      (node (ref "H1") (pin "B3,2") (pinfunction "MOUNT_B3,2") (pintype "passive"))
    )
    (net (code "91") (name "unconnected-(H2-MOUNT-PadB3,2)") (class "Default")
      (node (ref "H2") (pin "B3,2") (pinfunction "MOUNT_B3,2") (pintype "passive"))
    )
    (net (code "92") (name "unconnected-(H4-MOUNT-PadB3,2)") (class "Default")
      (node (ref "H4") (pin "B3,2") (pinfunction "MOUNT_B3,2") (pintype "passive"))
    )
    (net (code "93") (name "unconnected-(IC3-INTA-Pad20)") (class "Default")
      (node (ref "IC3") (pin "20") (pinfunction "INTA_20") (pintype "output"))
    )
    (net (code "94") (name "unconnected-(IC3-INTB-Pad19)") (class "Default")
      (node (ref "IC3") (pin "19") (pinfunction "INTB_19") (pintype "output"))
    )
    (net (code "95") (name "unconnected-(IC5-INTA-Pad20)") (class "Default")
      (node (ref "IC5") (pin "20") (pinfunction "INTA_20") (pintype "output"))
    )
    (net (code "96") (name "unconnected-(IC5-INTB-Pad19)") (class "Default")
      (node (ref "IC5") (pin "19") (pinfunction "INTB_19") (pintype "output"))
    )
    (net (code "97") (name "unconnected-(J1-SN-PadSLEEVE_I)") (class "Default")
      (node (ref "J1") (pin "SLEEVE_I") (pinfunction "SN_SLEEVE_I") (pintype "passive"))
    )
    (net (code "98") (name "unconnected-(J1-TN-PadTIP_I)") (class "Default")
      (node (ref "J1") (pin "TIP_I") (pinfunction "TN_TIP_I") (pintype "passive"))
    )
    (net (code "99") (name "unconnected-(JP1-Pad5)") (class "Default")
      (node (ref "JP1") (pin "5") (pinfunction "5_5") (pintype "passive"))
    )
    (net (code "100") (name "unconnected-(JP1-Pad6)") (class "Default")
      (node (ref "JP1") (pin "6") (pinfunction "6_6") (pintype "passive"))
    )
    (net (code "101") (name "unconnected-(JP1-Pad7)") (class "Default")
      (node (ref "JP1") (pin "7") (pinfunction "7_7") (pintype "passive"))
    )
    (net (code "102") (name "unconnected-(LINK-MOUNT-PadB3,2)") (class "Default")
      (node (ref "LINK") (pin "B3,2") (pinfunction "MOUNT_B3,2") (pintype "passive"))
    )
    (net (code "103") (name "unconnected-(PERC_3NDA-O-PadUN)") (class "Default")
      (node (ref "PERC_3ND") (pin "UN") (pinfunction "O_UN") (pintype "passive"))
    )
    (net (code "104") (name "unconnected-(PERC_FASTA-O-PadUN)") (class "Default")
      (node (ref "PERC_FAST") (pin "UN") (pinfunction "O_UN") (pintype "passive"))
    )
    (net (code "105") (name "unconnected-(PERC_ONA-O-PadUN)") (class "Default")
      (node (ref "PERC_ON") (pin "UN") (pinfunction "O_UN") (pintype "passive"))
    )
    (net (code "106") (name "unconnected-(PERC_SOFTA-O-PadUN)") (class "Default")
      (node (ref "PERC_SOFT") (pin "UN") (pinfunction "O_UN") (pintype "passive"))
    )
    (net (code "107") (name "unconnected-(SEL-S-Pad1)") (class "Default")
      (node (ref "SEL") (pin "1") (pinfunction "S_1") (pintype "passive"))
    )
    (net (code "108") (name "unconnected-(SHIFT-S-Pad1)") (class "Default")
      (node (ref "SHIFT") (pin "1") (pinfunction "S_1") (pintype "passive"))
    )
    (net (code "109") (name "unconnected-(SLOW_FASTA-O-PadUN)") (class "Default")
      (node (ref "SLOW_FAST") (pin "UN") (pinfunction "O_UN") (pintype "passive"))
    )
    (net (code "110") (name "unconnected-(START_STOPA-O-PadUN)") (class "Default")
      (node (ref "START_STOP") (pin "UN") (pinfunction "O_UN") (pintype "passive"))
    )
    (net (code "111") (name "unconnected-(U$1-Pad3)") (class "Default")
      (node (ref "U$1") (pin "3") (pinfunction "3_3") (pintype "bidirectional"))
    )
    (net (code "112") (name "unconnected-(U$1-Pad4)") (class "Default")
      (node (ref "U$1") (pin "4") (pinfunction "4_4") (pintype "bidirectional"))
    )
    (net (code "113") (name "unconnected-(VIB_ONA-O-PadUN)") (class "Default")
      (node (ref "VIB_ON") (pin "UN") (pinfunction "O_UN") (pintype "passive"))
    )
    (net (code "114") (name "unconnected-(VIB_SELA-O-PadUN)") (class "Default")
      (node (ref "VIB_SEL") (pin "UN") (pinfunction "O_UN") (pintype "passive"))
    )
  )
)
